# 5V_3V3_LDO.net
KiCad netlist of a schematic drawn in Altium Designer
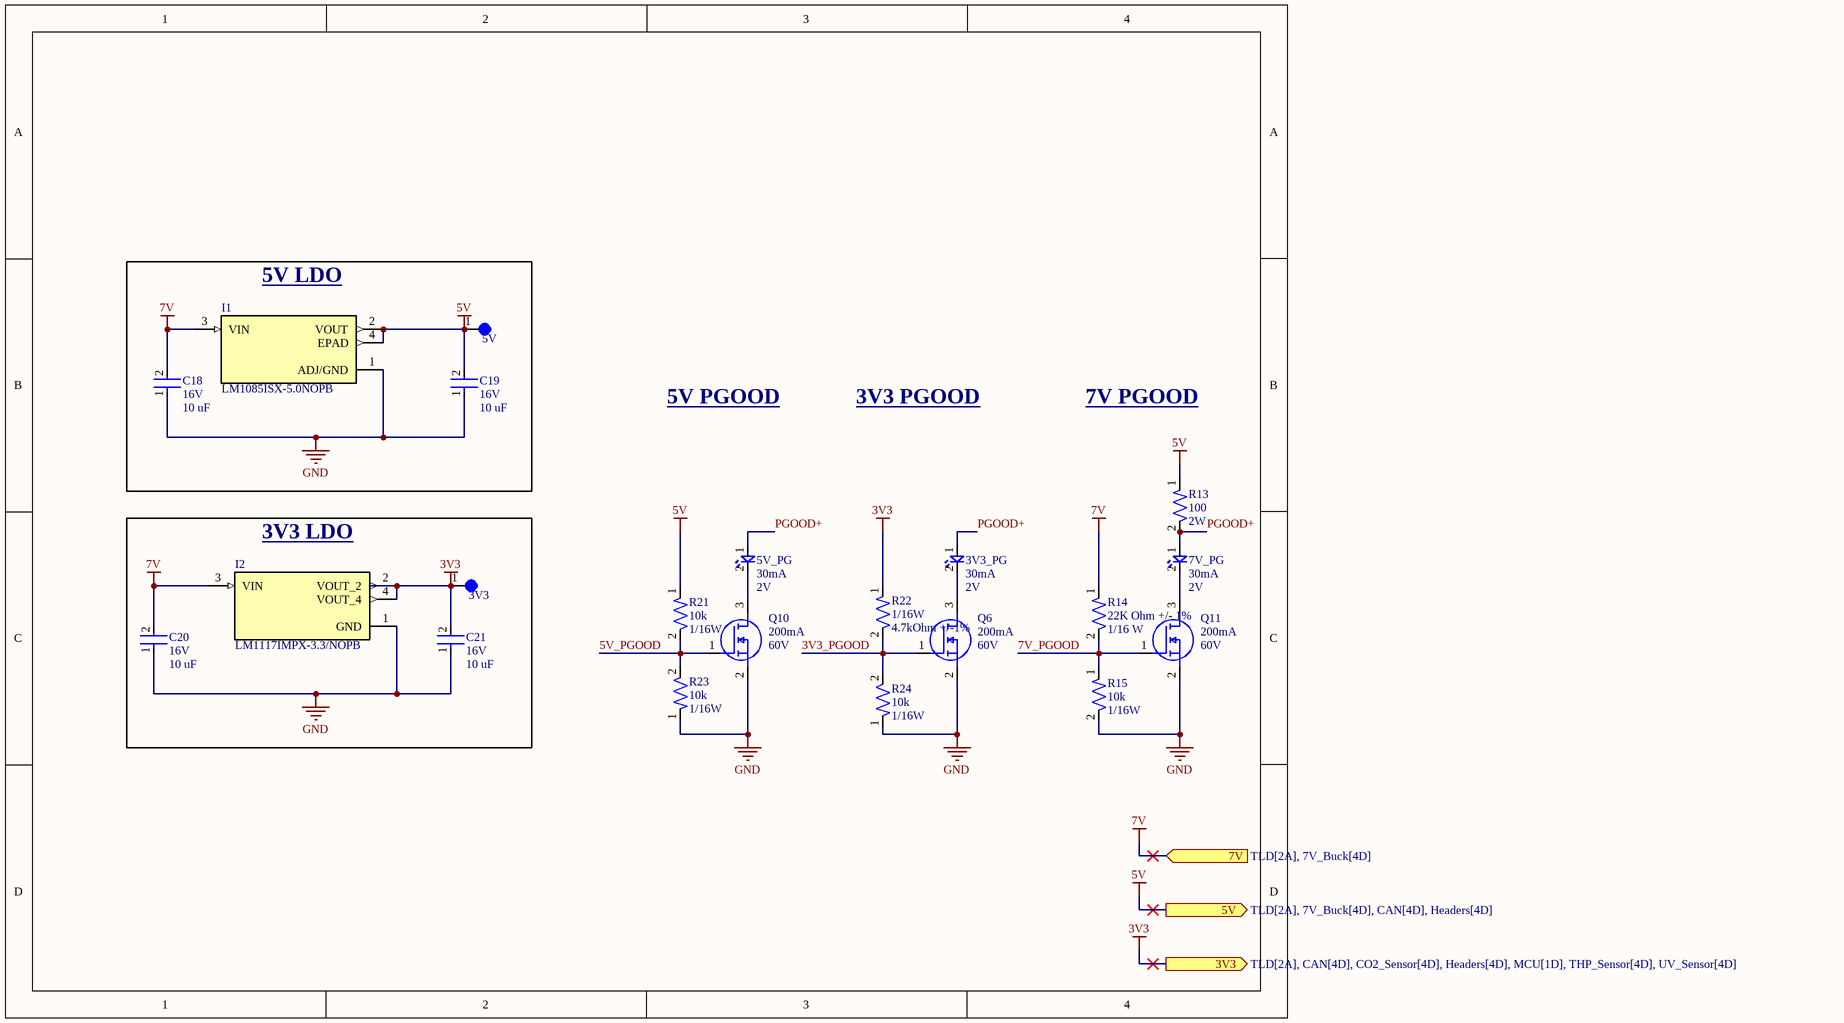
[diagram p0: 5V_3V3_LDO.SchDoc]

(export (version "E")
  (design (tool "Eeschema 10.0.6"))
  (components
    (comp (ref "3V3")
      (value "5003")
      (footprint "TEST-POINT-0001")
      (description "Oranange PC Test Point, Miniature Phoisphor Bronze Silver Plating Through Hole Mounting Type")
      (libsource (lib "JLC_25") (part "TEST-POINT-0001"))
    )
    (comp (ref "3V3_PG")
      (value "BL-HKC36G-AV-TRB")
      (footprint "LED-0603")
      (description "LED YELLOW CLEAR 0603 SMD")
      (fields (field (name "FORWARD CURRENT") "30mA") (field (name "FORWARD VOLTAGE") "2V"))
      (libsource (lib "JLC_25") (part "LED-0001"))
    )
    (comp (ref "5V")
      (value "5003")
      (footprint "TEST-POINT-0001")
      (description "Oranange PC Test Point, Miniature Phoisphor Bronze Silver Plating Through Hole Mounting Type")
      (libsource (lib "JLC_25") (part "TEST-POINT-0001"))
    )
    (comp (ref "5V_PG")
      (value "BL-HKC36G-AV-TRB")
      (footprint "LED-0603")
      (description "LED YELLOW CLEAR 0603 SMD")
      (fields (field (name "FORWARD CURRENT") "30mA") (field (name "FORWARD VOLTAGE") "2V"))
      (libsource (lib "JLC_25") (part "LED-0001"))
    )
    (comp (ref "7V_PG")
      (value "BL-HKC36G-AV-TRB")
      (footprint "LED-0603")
      (description "LED YELLOW CLEAR 0603 SMD")
      (fields (field (name "FORWARD CURRENT") "30mA") (field (name "FORWARD VOLTAGE") "2V"))
      (libsource (lib "JLC_25") (part "LED-0001"))
    )
    (comp (ref "C18")
      (value "293D106X9016A2TE3")
      (footprint "CAP-1206")
      (description "CAP TANT 10UF 10% 16V 1206")
      (fields (field (name "VOLTAGE") "16V") (field (name "CAPACITANCE") "10 uF"))
      (libsource (lib "JLC_25") (part "CAP-10U-0004"))
    )
    (comp (ref "C19")
      (value "293D106X9016A2TE3")
      (footprint "CAP-1206")
      (description "CAP TANT 10UF 10% 16V 1206")
      (fields (field (name "VOLTAGE") "16V") (field (name "CAPACITANCE") "10 uF"))
      (libsource (lib "JLC_25") (part "CAP-10U-0004"))
    )
    (comp (ref "C20")
      (value "293D106X9016A2TE3")
      (footprint "CAP-1206")
      (description "CAP TANT 10UF 10% 16V 1206")
      (fields (field (name "VOLTAGE") "16V") (field (name "CAPACITANCE") "10 uF"))
      (libsource (lib "JLC_25") (part "CAP-10U-0004"))
    )
    (comp (ref "C21")
      (value "293D106X9016A2TE3")
      (footprint "CAP-1206")
      (description "CAP TANT 10UF 10% 16V 1206")
      (fields (field (name "VOLTAGE") "16V") (field (name "CAPACITANCE") "10 uF"))
      (libsource (lib "JLC_25") (part "CAP-10U-0004"))
    )
    (comp (ref "I1")
      (value "LM1085ISX-5.0NOPB")
      (footprint "IC-TO-263-4")
      (description "IC REG LIN 5V 3A DDPAK/TO263-3")
      (libsource (lib "JLC_25") (part "IC_LDO_5V_0002"))
    )
    (comp (ref "I2")
      (value "LM1117IMPX-3.3/NOPB")
      (footprint "IC-SOT-223-4")
      (description "IC REG LIN 3.3V 800MA SOT223-4")
      (libsource (lib "JLC_25") (part "IC_LDO_3V3_0001"))
    )
    (comp (ref "Q6")
      (value "T2N7002AK,LM")
      (footprint "IC-SOT23-3")
      (description "MOSFET N-CH 60V 200MA SOT23")
      (fields (field (name "CONTINUOUS CURRENT") "200mA") (field (name "VOLTAGE") "60V"))
      (libsource (lib "JLC_25") (part "NMOS-200MA-0001"))
    )
    (comp (ref "Q10")
      (value "T2N7002AK,LM")
      (footprint "IC-SOT23-3")
      (description "MOSFET N-CH 60V 200MA SOT23")
      (fields (field (name "CONTINUOUS CURRENT") "200mA") (field (name "VOLTAGE") "60V"))
      (libsource (lib "JLC_25") (part "NMOS-200MA-0001"))
    )
    (comp (ref "Q11")
      (value "T2N7002AK,LM")
      (footprint "IC-SOT23-3")
      (description "MOSFET N-CH 60V 200MA SOT23")
      (fields (field (name "CONTINUOUS CURRENT") "200mA") (field (name "VOLTAGE") "60V"))
      (libsource (lib "JLC_25") (part "NMOS-200MA-0001"))
    )
    (comp (ref "R13")
      (value "SR2512JK-7W100RL")
      (footprint "RESC6331X65N")
      (fields
        (field (name "MF") "{'manufacturer': u'YAGEO'}")
        (field (name "RESISTANCE") "100")
        (field (name "POWER") "2W")
      )
      (libsource (lib "JLC_25") (part "RES-100-0002"))
    )
    (comp (ref "R14")
      (value "AC0402FR-0722KL")
      (footprint "RES-0402")
      (fields
        (field (name "JLC PART NUMBER") "C144778")
        (field (name "RESISTANCE") "22K Ohm +/- 1%")
        (field (name "POWER") "1/16 W")
      )
      (libsource (lib "MasterLib") (part "RES-22K-0002-JLC"))
    )
    (comp (ref "R15")
      (value "RC0402FR-0710KL")
      (footprint "RES-0402")
      (description "RES 10K OHM 1% 1/16W 0402")
      (fields
        (field (name "TOLERANCE") "1%")
        (field (name "RESISTANCE") "10k")
        (field (name "POWER") "1/16W")
      )
      (libsource (lib "JLC_25") (part "RES-10k-0001"))
    )
    (comp (ref "R21")
      (value "RC0402FR-0710KL")
      (footprint "RES-0402")
      (description "RES 10K OHM 1% 1/16W 0402")
      (fields
        (field (name "TOLERANCE") "1%")
        (field (name "RESISTANCE") "10k")
        (field (name "POWER") "1/16W")
      )
      (libsource (lib "JLC_25") (part "RES-10k-0001"))
    )
    (comp (ref "R22")
      (value "RC0402FR-074K7P")
      (footprint "RES-0402")
      (description "RES SMD 4.7K OHM 1% 1/16W 0402")
      (fields
        (field (name "MANUFACTURER") "YAGEO")
        (field (name "POWER RATING") "1/16W")
        (field (name "RESISTANCE") "4.7kOhm +/-1%")
      )
      (libsource (lib "MasterLib") (part "RES-4.7K-0001"))
    )
    (comp (ref "R23")
      (value "RC0402FR-0710KL")
      (footprint "RES-0402")
      (description "RES 10K OHM 1% 1/16W 0402")
      (fields
        (field (name "TOLERANCE") "1%")
        (field (name "RESISTANCE") "10k")
        (field (name "POWER") "1/16W")
      )
      (libsource (lib "JLC_25") (part "RES-10k-0001"))
    )
    (comp (ref "R24")
      (value "RC0402FR-0710KL")
      (footprint "RES-0402")
      (description "RES 10K OHM 1% 1/16W 0402")
      (fields
        (field (name "TOLERANCE") "1%")
        (field (name "RESISTANCE") "10k")
        (field (name "POWER") "1/16W")
      )
      (libsource (lib "JLC_25") (part "RES-10k-0001"))
    )
  )
  (nets
    (net (code "1") (name "/3V3_PGOOD") (class "Default")
      (node (ref "Q6") (pin "1") (pinfunction "G_1") (pintype "passive"))
      (node (ref "R22") (pin "2") (pinfunction "2_2") (pintype "passive"))
      (node (ref "R24") (pin "2") (pinfunction "2_2") (pintype "passive"))
    )
    (net (code "2") (name "/5V_PGOOD") (class "Default")
      (node (ref "Q10") (pin "1") (pinfunction "G_1") (pintype "passive"))
      (node (ref "R21") (pin "2") (pinfunction "2_2") (pintype "passive"))
      (node (ref "R23") (pin "2") (pinfunction "2_2") (pintype "passive"))
    )
    (net (code "3") (name "/7V_PGOOD") (class "Default")
      (node (ref "Q11") (pin "1") (pinfunction "G_1") (pintype "passive"))
      (node (ref "R14") (pin "2") (pinfunction "2_2") (pintype "passive"))
      (node (ref "R15") (pin "1") (pinfunction "1_1") (pintype "passive"))
    )
    (net (code "4") (name "/PGOOD+") (class "Default")
      (node (ref "3V3_PG") (pin "1") (pinfunction "1_1") (pintype "passive"))
      (node (ref "5V_PG") (pin "1") (pinfunction "1_1") (pintype "passive"))
      (node (ref "7V_PG") (pin "1") (pinfunction "1_1") (pintype "passive"))
      (node (ref "R13") (pin "2") (pinfunction "2_2") (pintype "passive"))
    )
    (net (code "5") (name "3V3") (class "Default")
      (node (ref "3V3") (pin "1") (pinfunction "0_1") (pintype "passive"))
      (node (ref "C21") (pin "2") (pinfunction "2_2") (pintype "passive"))
      (node (ref "I2") (pin "2") (pinfunction "VOUT_2_2") (pintype "output"))
      (node (ref "I2") (pin "4") (pinfunction "VOUT_4_4") (pintype "output"))
      (node (ref "R22") (pin "1") (pinfunction "1_1") (pintype "passive"))
    )
    (net (code "6") (name "5V") (class "Default")
      (node (ref "5V") (pin "1") (pinfunction "0_1") (pintype "passive"))
      (node (ref "C19") (pin "2") (pinfunction "2_2") (pintype "passive"))
      (node (ref "I1") (pin "2") (pinfunction "VOUT_2") (pintype "output"))
      (node (ref "I1") (pin "4") (pinfunction "EPAD_4") (pintype "output"))
      (node (ref "R13") (pin "1") (pinfunction "1_1") (pintype "passive"))
      (node (ref "R21") (pin "1") (pinfunction "1_1") (pintype "passive"))
    )
    (net (code "7") (name "7V") (class "Default")
      (node (ref "C18") (pin "2") (pinfunction "2_2") (pintype "passive"))
      (node (ref "C20") (pin "2") (pinfunction "2_2") (pintype "passive"))
      (node (ref "I1") (pin "3") (pinfunction "VIN_3") (pintype "input"))
      (node (ref "I2") (pin "3") (pinfunction "VIN_3") (pintype "input"))
      (node (ref "R14") (pin "1") (pinfunction "1_1") (pintype "passive"))
    )
    (net (code "8") (name "GND") (class "Default")
      (node (ref "C18") (pin "1") (pinfunction "1_1") (pintype "passive"))
      (node (ref "C19") (pin "1") (pinfunction "1_1") (pintype "passive"))
      (node (ref "C20") (pin "1") (pinfunction "1_1") (pintype "passive"))
      (node (ref "C21") (pin "1") (pinfunction "1_1") (pintype "passive"))
      (node (ref "I1") (pin "1") (pinfunction "ADJ/GND_1") (pintype "power_in"))
      (node (ref "I2") (pin "1") (pinfunction "GND_1") (pintype "power_in"))
      (node (ref "Q10") (pin "2") (pinfunction "S_2") (pintype "passive"))
      (node (ref "Q11") (pin "2") (pinfunction "S_2") (pintype "passive"))
      (node (ref "Q6") (pin "2") (pinfunction "S_2") (pintype "passive"))
      (node (ref "R15") (pin "2") (pinfunction "2_2") (pintype "passive"))
      (node (ref "R23") (pin "1") (pinfunction "1_1") (pintype "passive"))
      (node (ref "R24") (pin "1") (pinfunction "1_1") (pintype "passive"))
    )
    (net (code "9") (name "Net-(Q6-D)") (class "Default")
      (node (ref "3V3_PG") (pin "2") (pinfunction "2_2") (pintype "passive"))
      (node (ref "Q6") (pin "3") (pinfunction "D_3") (pintype "passive"))
    )
    (net (code "10") (name "Net-(Q10-D)") (class "Default")
      (node (ref "5V_PG") (pin "2") (pinfunction "2_2") (pintype "passive"))
      (node (ref "Q10") (pin "3") (pinfunction "D_3") (pintype "passive"))
    )
    (net (code "11") (name "Net-(Q11-D)") (class "Default")
      (node (ref "7V_PG") (pin "2") (pinfunction "2_2") (pintype "passive"))
      (node (ref "Q11") (pin "3") (pinfunction "D_3") (pintype "passive"))
    )
  )
)
